# 2_MCU.net
KiCad netlist of a schematic drawn in Altium Designer
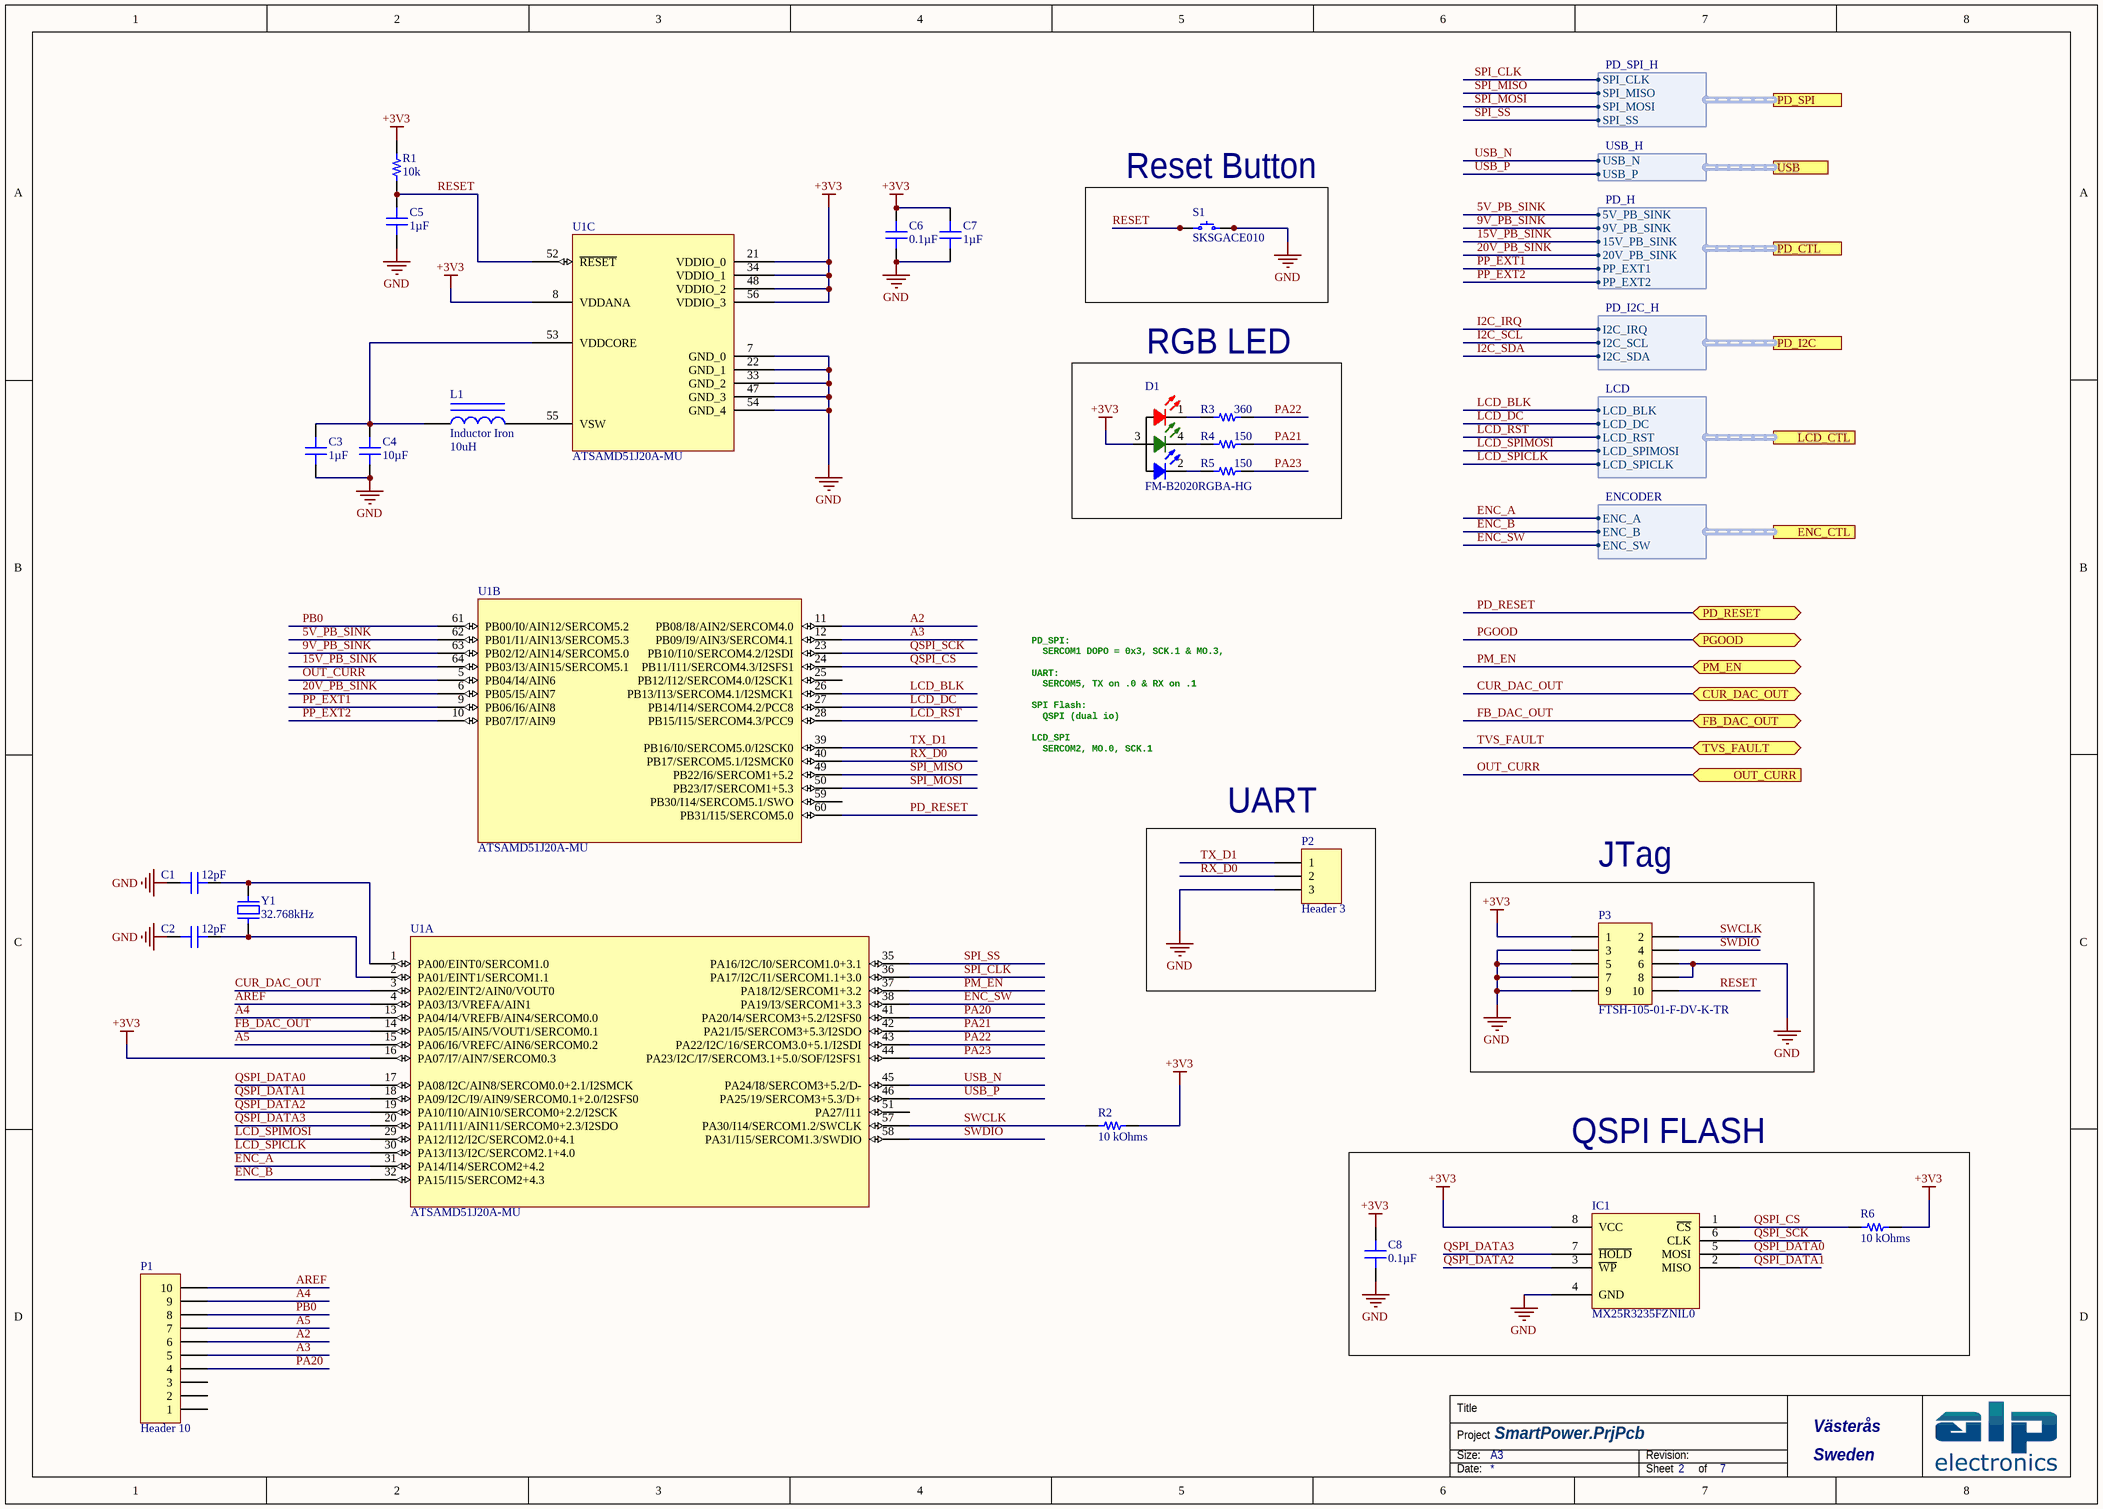
[diagram p0: [2] MCU.SchDoc]

(export (version "E")
  (design (tool "Eeschema 10.0.6"))
  (components
    (comp (ref "C1")
      (value "12pF")
      (footprint "CAP 0603_1608")
      (description "CAP CER 12PF 100V NP0 0603")
      (fields (field (name "PART NUMBER") "06031A120JAT4A") (field (name "MANUFACTURER") "AVX Corporation"))
      (libsource (lib "Celestial Altium Library - altium_library") (part "Capacitor"))
    )
    (comp (ref "C2")
      (value "12pF")
      (footprint "CAP 0603_1608")
      (description "CAP CER 12PF 100V NP0 0603")
      (fields (field (name "PART NUMBER") "06031A120JAT4A") (field (name "MANUFACTURER") "AVX Corporation"))
      (libsource (lib "Celestial Altium Library - altium_library") (part "Capacitor"))
    )
    (comp (ref "C3")
      (value "1µF")
      (footprint "CAP 0603_1608")
      (description "CAP CER 1UF 50V X7R 0603")
      (fields (field (name "PART NUMBER") "06035C105KAT2A") (field (name "MANUFACTURER") "AVX Corporation"))
      (libsource (lib "Celestial Altium Library - altium_library") (part "Capacitor"))
    )
    (comp (ref "C4")
      (value "10µF")
      (footprint "CAP 0603_1608")
      (description "CAP CER 10UF 10V X5R 0603")
      (fields (field (name "PART NUMBER") "0603ZD106MAT2A") (field (name "MANUFACTURER") "AVX Corporation"))
      (libsource (lib "Celestial Altium Library - altium_library") (part "Capacitor"))
    )
    (comp (ref "C5")
      (value "1µF")
      (footprint "CAP 0603_1608")
      (description "CAP CER 1UF 50V X7R 0603")
      (fields (field (name "PART NUMBER") "06035C105KAT2A") (field (name "MANUFACTURER") "AVX Corporation"))
      (libsource (lib "Celestial Altium Library - altium_library") (part "Capacitor"))
    )
    (comp (ref "C6")
      (value "0.1µF")
      (footprint "CAP 0603_1608")
      (description "CAP CER 0.1UF 50V X7R 0603")
      (fields (field (name "PART NUMBER") "0603BB104K500NGT") (field (name "MANUFACTURER") "Knowles Novacap"))
      (libsource (lib "Celestial Altium Library - altium_library") (part "Capacitor"))
    )
    (comp (ref "C7")
      (value "1µF")
      (footprint "CAP 0603_1608")
      (description "CAP CER 1UF 16V X7R 0603")
      (fields (field (name "PART NUMBER") "0603BB105K160YT") (field (name "MANUFACTURER") "Knowles Novacap"))
      (libsource (lib "Celestial Altium Library - altium_library") (part "Capacitor"))
    )
    (comp (ref "C8")
      (value "0.1µF")
      (footprint "CAP 0603_1608")
      (description "CAP CER 0.1UF 50V X7R 0603")
      (fields (field (name "PART NUMBER") "0603BB104K500NGT") (field (name "MANUFACTURER") "Knowles Novacap"))
      (libsource (lib "Celestial Altium Library - altium_library") (part "Capacitor"))
    )
    (comp (ref "D1")
      (value "FM-B2020RGBA-HG")
      (footprint "FM-B2020RGBA-HG")
      (description "RGB 615~630nmRed,515~535nmGreen,465~480nmBlue 2020")
      (fields (field (name "MANUFACTURER") "Foshan NationStar Optoelectronics"))
      (libsource (lib "Celestial Library Database") (part "RGB LED 4PIN"))
    )
    (comp (ref "IC1")
      (value "MX25R3235FZNIL0")
      (footprint "SPANSION WSON-8 6x5MM")
      (description "IC FLASH MEM 16MB SPI CMOS 8WSON")
      (fields (field (name "PART NUMBER") "S25FL116K0XNFI011") (field (name "MANUFACTURER") "Spansion"))
      (libsource (lib "Celestial Library Database") (part "SPANSION FLASH SPI 8PIN"))
    )
    (comp (ref "L1")
      (value "Inductor Iron")
      (footprint "Component 3D Footprint:IND_Würth_74404020100")
      (description "Magnetic-Core Inductor")
      (fields (field (name "ALTIUM_VALUE") "10uH") (field (name "PUBLISHER") "Altium Limited"))
      (libsource (lib "Miscellaneous Devices") (part "Inductor Iron"))
    )
    (comp (ref "P1")
      (value "Header 10")
      (footprint "HDR1X10")
      (description "Header, 10-Pin")
      (fields (field (name "PUBLISHER") "Altium Limited"))
      (libsource (lib "Miscellaneous Connectors") (part "Header 10"))
    )
    (comp (ref "P2")
      (value "Header 3")
      (footprint "HDR1X3")
      (description "Header, 3-Pin")
      (fields (field (name "PUBLISHER") "Altium Limited"))
      (libsource (lib "Miscellaneous Connectors") (part "Header 3"))
    )
    (comp (ref "P3")
      (value "FTSH-105-01-F-DV-K-TR")
      (footprint "3D FootPrint_Backup:FTSH-105-01-F-DV-K-TR")
      (description "Header, 5-Pin, Dual row")
      (fields (field (name "PUBLISHER") "Altium Limited"))
      (libsource (lib "Miscellaneous Connectors") (part "Header 5X2"))
    )
    (comp (ref "R1")
      (value "10k")
      (footprint "RES 0603/1608")
      (description "RES SMD 10K OHM 5% 1/10W 0603")
      (fields
        (field (name "PART NUMBER") "ERJ-3GEYJ103V")
        (field (name "MANUFACTURER") "Panasonic Electronic Components")
      )
      (libsource (lib "Celestial Library Database") (part "Resistor"))
    )
    (comp (ref "R2")
      (value "10 kOhms")
      (footprint "RES 0603_1608")
      (description "RES SMD 10K OHM 5% 1/10W 0603")
      (fields (field (name "PART NUMBER") "CRCW060310K0JNEA") (field (name "MANUFACTURER") "Vishay Dale"))
      (libsource (lib "Celestial Altium Library - altium_library") (part "Resistor"))
    )
    (comp (ref "R3")
      (value "360")
      (footprint "RES 0603/1608")
      (description "RES SMD 360 OHM 5% 1/10W 0603")
      (fields
        (field (name "PART NUMBER") "ERJ-3GEYJ361V")
        (field (name "MANUFACTURER") "Panasonic Electronic Components")
      )
      (libsource (lib "Celestial Library Database") (part "Resistor"))
    )
    (comp (ref "R4")
      (value "150")
      (footprint "RES 0603/1608")
      (description "RES SMD 150 OHM 5% 1/10W 0603")
      (fields
        (field (name "PART NUMBER") "ERJ-3GEYJ151V")
        (field (name "MANUFACTURER") "Panasonic Electronic Components")
      )
      (libsource (lib "Celestial Library Database") (part "Resistor"))
    )
    (comp (ref "R5")
      (value "150")
      (footprint "RES 0603/1608")
      (description "RES SMD 150 OHM 5% 1/10W 0603")
      (fields
        (field (name "PART NUMBER") "ERJ-3GEYJ151V")
        (field (name "MANUFACTURER") "Panasonic Electronic Components")
      )
      (libsource (lib "Celestial Library Database") (part "Resistor"))
    )
    (comp (ref "R6")
      (value "10 kOhms")
      (footprint "RES 0603_1608")
      (description "RES SMD 10K OHM 5% 1/10W 0603")
      (fields (field (name "PART NUMBER") "CRCW060310K0JNEA") (field (name "MANUFACTURER") "Vishay Dale"))
      (libsource (lib "Celestial Altium Library - altium_library") (part "Resistor"))
    )
    (comp (ref "S1")
      (value "SKSGACE010")
      (footprint "SKSGACE010")
      (description "SWITCH TACTILE SPST-NO 0.05A 16V")
      (fields (field (name "MANUFACTURER") "ALPS"))
      (libsource (lib "Celestial Library Database") (part "SPST-NO 4 PIN"))
    )
    (comp (ref "U1")
      (value "ATSAMD51J20A-MU")
      (footprint "SI LABS QFN-64_S")
      (description "IC MCU 32BIT 1MB FLASH 64VQFN")
      (fields (field (name "MANUFACTURER") "Microchip Technology"))
      (libsource (lib "Celestial Library Database") (part "MicroChip SAM D5x VQFN64"))
    )
    (comp (ref "Y1")
      (value "32.768kHz")
      (footprint "ABRACON ABS07")
      (description "CRYSTAL 32.7680KHZ 12.5PF SMD")
      (fields (field (name "PART NUMBER") "ABS07-32.768KHZ-T") (field (name "MANUFACTURER") "Abracon LLC"))
      (libsource (lib "Celestial Library Database") (part "Abracon Crystal ABS07"))
    )
  )
  (nets
    (net (code "7") (name "+3V3") (class "Default")
      (node (ref "C6") (pin "1") (pinfunction "1_1") (pintype "passive"))
      (node (ref "C7") (pin "2") (pinfunction "2_2") (pintype "passive"))
      (node (ref "C8") (pin "1") (pinfunction "1_1") (pintype "passive"))
      (node (ref "D1") (pin "3") (pinfunction "3_3") (pintype "passive"))
      (node (ref "IC1") (pin "8") (pinfunction "VCC_8") (pintype "passive"))
      (node (ref "P3") (pin "1") (pinfunction "1_1") (pintype "passive"))
      (node (ref "R1") (pin "2") (pinfunction "2_2") (pintype "passive"))
      (node (ref "R2") (pin "2") (pinfunction "2_2") (pintype "passive"))
      (node (ref "R6") (pin "2") (pinfunction "2_2") (pintype "passive"))
      (node (ref "U1") (pin "16") (pinfunction "PA07/I7/AIN7/SERCOM0.3_16") (pintype "bidirectional"))
      (node (ref "U1") (pin "21") (pinfunction "VDDIO_0_21") (pintype "power_in"))
      (node (ref "U1") (pin "34") (pinfunction "VDDIO_1_34") (pintype "power_in"))
      (node (ref "U1") (pin "48") (pinfunction "VDDIO_2_48") (pintype "power_in"))
      (node (ref "U1") (pin "56") (pinfunction "VDDIO_3_56") (pintype "power_in"))
      (node (ref "U1") (pin "8") (pinfunction "VDDANA_8") (pintype "power_in"))
    )
    (net (code "8") (name "/5V_PB_SINK") (class "Default")
      (node (ref "U1") (pin "62") (pinfunction "PB01/I1/AIN13/SERCOM5.3_62") (pintype "bidirectional"))
    )
    (net (code "9") (name "/9V_PB_SINK") (class "Default")
      (node (ref "U1") (pin "63") (pinfunction "PB02/I2/AIN14/SERCOM5.0_63") (pintype "bidirectional"))
    )
    (net (code "10") (name "/15V_PB_SINK") (class "Default")
      (node (ref "U1") (pin "64") (pinfunction "PB03/I3/AIN15/SERCOM5.1_64") (pintype "bidirectional"))
    )
    (net (code "11") (name "/20V_PB_SINK") (class "Default")
      (node (ref "U1") (pin "6") (pinfunction "PB05/I5/AIN7_6") (pintype "bidirectional"))
    )
    (net (code "12") (name "/A2") (class "Default")
      (node (ref "P1") (pin "6") (pinfunction "6_6") (pintype "passive"))
      (node (ref "U1") (pin "11") (pinfunction "PB08/I8/AIN2/SERCOM4.0_11") (pintype "bidirectional"))
    )
    (net (code "13") (name "/A3") (class "Default")
      (node (ref "P1") (pin "5") (pinfunction "5_5") (pintype "passive"))
      (node (ref "U1") (pin "12") (pinfunction "PB09/I9/AIN3/SERCOM4.1_12") (pintype "bidirectional"))
    )
    (net (code "14") (name "/A4") (class "Default")
      (node (ref "P1") (pin "9") (pinfunction "9_9") (pintype "passive"))
      (node (ref "U1") (pin "13") (pinfunction "PA04/I4/VREFB/AIN4/SERCOM0.0_13") (pintype "bidirectional"))
    )
    (net (code "15") (name "/A5") (class "Default")
      (node (ref "P1") (pin "7") (pinfunction "7_7") (pintype "passive"))
      (node (ref "U1") (pin "15") (pinfunction "PA06/I6/VREFC/AIN6/SERCOM0.2_15") (pintype "bidirectional"))
    )
    (net (code "16") (name "/AREF") (class "Default")
      (node (ref "P1") (pin "10") (pinfunction "10_10") (pintype "passive"))
      (node (ref "U1") (pin "4") (pinfunction "PA03/I3/VREFA/AIN1_4") (pintype "bidirectional"))
    )
    (net (code "17") (name "/CUR_DAC_OUT") (class "Default")
      (node (ref "U1") (pin "3") (pinfunction "PA02/EINT2/AIN0/VOUT0_3") (pintype "bidirectional"))
    )
    (net (code "18") (name "/ENC_A") (class "Default")
      (node (ref "U1") (pin "31") (pinfunction "PA14/I14/SERCOM2+4.2_31") (pintype "bidirectional"))
    )
    (net (code "19") (name "/ENC_B") (class "Default")
      (node (ref "U1") (pin "32") (pinfunction "PA15/I15/SERCOM2+4.3_32") (pintype "bidirectional"))
    )
    (net (code "20") (name "/ENC_SW") (class "Default")
      (node (ref "U1") (pin "38") (pinfunction "PA19/I3/SERCOM1+3.3_38") (pintype "bidirectional"))
    )
    (net (code "21") (name "/FB_DAC_OUT") (class "Default")
      (node (ref "U1") (pin "14") (pinfunction "PA05/I5/AIN5/VOUT1/SERCOM0.1_14") (pintype "bidirectional"))
    )
    (net (code "25") (name "/LCD_BLK") (class "Default")
      (node (ref "U1") (pin "26") (pinfunction "PB13/I13/SERCOM4.1/I2SMCK1_26") (pintype "bidirectional"))
    )
    (net (code "26") (name "/LCD_DC") (class "Default")
      (node (ref "U1") (pin "27") (pinfunction "PB14/I14/SERCOM4.2/PCC8_27") (pintype "bidirectional"))
    )
    (net (code "27") (name "/LCD_RST") (class "Default")
      (node (ref "U1") (pin "28") (pinfunction "PB15/I15/SERCOM4.3/PCC9_28") (pintype "bidirectional"))
    )
    (net (code "28") (name "/LCD_SPICLK") (class "Default")
      (node (ref "U1") (pin "30") (pinfunction "PA13/I13/I2C/SERCOM2.1+4.0_30") (pintype "bidirectional"))
    )
    (net (code "29") (name "/LCD_SPIMOSI") (class "Default")
      (node (ref "U1") (pin "29") (pinfunction "PA12/I12/I2C/SERCOM2.0+4.1_29") (pintype "bidirectional"))
    )
    (net (code "30") (name "/OUT_CURR") (class "Default")
      (node (ref "U1") (pin "5") (pinfunction "PB04/I4/AIN6_5") (pintype "bidirectional"))
    )
    (net (code "31") (name "/PA20") (class "Default")
      (node (ref "P1") (pin "4") (pinfunction "4_4") (pintype "passive"))
      (node (ref "U1") (pin "41") (pinfunction "PA20/I4/SERCOM3+5.2/I2SFS0_41") (pintype "bidirectional"))
    )
    (net (code "32") (name "/PA21") (class "Default")
      (node (ref "R4") (pin "2") (pinfunction "2_2") (pintype "passive"))
      (node (ref "U1") (pin "42") (pinfunction "PA21/I5/SERCOM3+5.3/I2SDO_42") (pintype "bidirectional"))
    )
    (net (code "33") (name "/PA22") (class "Default")
      (node (ref "R3") (pin "2") (pinfunction "2_2") (pintype "passive"))
      (node (ref "U1") (pin "43") (pinfunction "PA22/I2C/16/SERCOM3.0+5.1/I2SDI_43") (pintype "bidirectional"))
    )
    (net (code "34") (name "/PA23") (class "Default")
      (node (ref "R5") (pin "2") (pinfunction "2_2") (pintype "passive"))
      (node (ref "U1") (pin "44") (pinfunction "PA23/I2C/I7/SERCOM3.1+5.0/SOF/I2SFS1_44") (pintype "bidirectional"))
    )
    (net (code "35") (name "/PB0") (class "Default")
      (node (ref "P1") (pin "8") (pinfunction "8_8") (pintype "passive"))
      (node (ref "U1") (pin "61") (pinfunction "PB00/I0/AIN12/SERCOM5.2_61") (pintype "bidirectional"))
    )
    (net (code "36") (name "/PD_RESET") (class "Default")
      (node (ref "U1") (pin "60") (pinfunction "PB31/I15/SERCOM5.0_60") (pintype "bidirectional"))
    )
    (net (code "38") (name "/PM_EN") (class "Default")
      (node (ref "U1") (pin "37") (pinfunction "PA18/I2/SERCOM1+3.2_37") (pintype "bidirectional"))
    )
    (net (code "39") (name "/PP_EXT1") (class "Default")
      (node (ref "U1") (pin "9") (pinfunction "PB06/I6/AIN8_9") (pintype "bidirectional"))
    )
    (net (code "40") (name "/PP_EXT2") (class "Default")
      (node (ref "U1") (pin "10") (pinfunction "PB07/I7/AIN9_10") (pintype "bidirectional"))
    )
    (net (code "41") (name "/QSPI_CS") (class "Default")
      (node (ref "IC1") (pin "1") (pinfunction "~{CS}_1") (pintype "passive"))
      (node (ref "R6") (pin "1") (pinfunction "1_1") (pintype "passive"))
      (node (ref "U1") (pin "24") (pinfunction "PB11/I11/SERCOM4.3/I2SFS1_24") (pintype "bidirectional"))
    )
    (net (code "42") (name "/QSPI_DATA0") (class "Default")
      (node (ref "IC1") (pin "5") (pinfunction "MOSI_5") (pintype "passive"))
      (node (ref "U1") (pin "17") (pinfunction "PA08/I2C/AIN8/SERCOM0.0+2.1/I2SMCK_17") (pintype "bidirectional"))
    )
    (net (code "43") (name "/QSPI_DATA1") (class "Default")
      (node (ref "IC1") (pin "2") (pinfunction "MISO_2") (pintype "passive"))
      (node (ref "U1") (pin "18") (pinfunction "PA09/I2C/I9/AIN9/SERCOM0.1+2.0/I2SFS0_18") (pintype "bidirectional"))
    )
    (net (code "44") (name "/QSPI_DATA2") (class "Default")
      (node (ref "IC1") (pin "3") (pinfunction "~{WP}_3") (pintype "passive"))
      (node (ref "U1") (pin "19") (pinfunction "PA10/I10/AIN10/SERCOM0+2.2/I2SCK_19") (pintype "bidirectional"))
    )
    (net (code "45") (name "/QSPI_DATA3") (class "Default")
      (node (ref "IC1") (pin "7") (pinfunction "~{HOLD}_7") (pintype "passive"))
      (node (ref "U1") (pin "20") (pinfunction "PA11/I11/AIN11/SERCOM0+2.3/I2SDO_20") (pintype "bidirectional"))
    )
    (net (code "46") (name "/QSPI_SCK") (class "Default")
      (node (ref "IC1") (pin "6") (pinfunction "CLK_6") (pintype "passive"))
      (node (ref "U1") (pin "23") (pinfunction "PB10/I10/SERCOM4.2/I2SDI_23") (pintype "bidirectional"))
    )
    (net (code "47") (name "/RESET") (class "Default")
      (node (ref "C5") (pin "2") (pinfunction "2_2") (pintype "passive"))
      (node (ref "P3") (pin "10") (pinfunction "10_10") (pintype "passive"))
      (node (ref "R1") (pin "1") (pinfunction "1_1") (pintype "passive"))
      (node (ref "S1") (pin "1") (pinfunction "1_1") (pintype "passive"))
      (node (ref "S1") (pin "2") (pinfunction "2_2") (pintype "passive"))
      (node (ref "U1") (pin "52") (pinfunction "~{RESET}_52") (pintype "bidirectional"))
    )
    (net (code "48") (name "/RX_D0") (class "Default")
      (node (ref "P2") (pin "2") (pinfunction "2_2") (pintype "passive"))
      (node (ref "U1") (pin "40") (pinfunction "PB17/SERCOM5.1/I2SMCK0_40") (pintype "bidirectional"))
    )
    (net (code "49") (name "/SPI_CLK") (class "Default")
      (node (ref "U1") (pin "36") (pinfunction "PA17/I2C/I1/SERCOM1.1+3.0_36") (pintype "bidirectional"))
    )
    (net (code "50") (name "/SPI_MISO") (class "Default")
      (node (ref "U1") (pin "49") (pinfunction "PB22/I6/SERCOM1+5.2_49") (pintype "bidirectional"))
    )
    (net (code "51") (name "/SPI_MOSI") (class "Default")
      (node (ref "U1") (pin "50") (pinfunction "PB23/I7/SERCOM1+5.3_50") (pintype "bidirectional"))
    )
    (net (code "52") (name "/SPI_SS") (class "Default")
      (node (ref "U1") (pin "35") (pinfunction "PA16/I2C/I0/SERCOM1.0+3.1_35") (pintype "bidirectional"))
    )
    (net (code "53") (name "/SWCLK") (class "Default")
      (node (ref "P3") (pin "2") (pinfunction "2_2") (pintype "passive"))
      (node (ref "R2") (pin "1") (pinfunction "1_1") (pintype "passive"))
      (node (ref "U1") (pin "57") (pinfunction "PA30/I14/SERCOM1.2/SWCLK_57") (pintype "bidirectional"))
    )
    (net (code "54") (name "/SWDIO") (class "Default")
      (node (ref "P3") (pin "4") (pinfunction "4_4") (pintype "passive"))
      (node (ref "U1") (pin "58") (pinfunction "PA31/I15/SERCOM1.3/SWDIO_58") (pintype "bidirectional"))
    )
    (net (code "56") (name "/TX_D1") (class "Default")
      (node (ref "P2") (pin "1") (pinfunction "1_1") (pintype "passive"))
      (node (ref "U1") (pin "39") (pinfunction "PB16/I0/SERCOM5.0/I2SCK0_39") (pintype "bidirectional"))
    )
    (net (code "57") (name "/USB_N") (class "Default")
      (node (ref "U1") (pin "45") (pinfunction "PA24/I8/SERCOM3+5.2/D-_45") (pintype "bidirectional"))
    )
    (net (code "58") (name "/USB_P") (class "Default")
      (node (ref "U1") (pin "46") (pinfunction "PA25/19/SERCOM3+5.3/D+_46") (pintype "bidirectional"))
    )
    (net (code "65") (name "GND") (class "Default")
      (node (ref "C1") (pin "1") (pinfunction "1_1") (pintype "passive"))
      (node (ref "C2") (pin "1") (pinfunction "1_1") (pintype "passive"))
      (node (ref "C3") (pin "1") (pinfunction "1_1") (pintype "passive"))
      (node (ref "C4") (pin "1") (pinfunction "1_1") (pintype "passive"))
      (node (ref "C5") (pin "1") (pinfunction "1_1") (pintype "passive"))
      (node (ref "C6") (pin "2") (pinfunction "2_2") (pintype "passive"))
      (node (ref "C7") (pin "1") (pinfunction "1_1") (pintype "passive"))
      (node (ref "C8") (pin "2") (pinfunction "2_2") (pintype "passive"))
      (node (ref "IC1") (pin "4") (pinfunction "GND_4") (pintype "passive"))
      (node (ref "P2") (pin "3") (pinfunction "3_3") (pintype "passive"))
      (node (ref "P3") (pin "3") (pinfunction "3_3") (pintype "passive"))
      (node (ref "P3") (pin "5") (pinfunction "5_5") (pintype "passive"))
      (node (ref "P3") (pin "6") (pinfunction "6_6") (pintype "passive"))
      (node (ref "P3") (pin "7") (pinfunction "7_7") (pintype "passive"))
      (node (ref "P3") (pin "8") (pinfunction "8_8") (pintype "passive"))
      (node (ref "P3") (pin "9") (pinfunction "9_9") (pintype "passive"))
      (node (ref "S1") (pin "3") (pinfunction "3_3") (pintype "passive"))
      (node (ref "S1") (pin "4") (pinfunction "4_4") (pintype "passive"))
      (node (ref "U1") (pin "22") (pinfunction "GND_1_22") (pintype "power_in"))
      (node (ref "U1") (pin "33") (pinfunction "GND_2_33") (pintype "power_in"))
      (node (ref "U1") (pin "47") (pinfunction "GND_3_47") (pintype "power_in"))
      (node (ref "U1") (pin "54") (pinfunction "GND_4_54") (pintype "power_in"))
      (node (ref "U1") (pin "7") (pinfunction "GND_0_7") (pintype "power_in"))
    )
    (net (code "66") (name "Net-(D1-Pad1)") (class "Default")
      (node (ref "D1") (pin "1") (pinfunction "1_1") (pintype "passive"))
      (node (ref "R3") (pin "1") (pinfunction "1_1") (pintype "passive"))
    )
    (net (code "67") (name "Net-(D1-Pad2)") (class "Default")
      (node (ref "D1") (pin "2") (pinfunction "2_2") (pintype "passive"))
      (node (ref "R5") (pin "1") (pinfunction "1_1") (pintype "passive"))
    )
    (net (code "68") (name "Net-(D1-Pad4)") (class "Default")
      (node (ref "D1") (pin "4") (pinfunction "4_4") (pintype "passive"))
      (node (ref "R4") (pin "1") (pinfunction "1_1") (pintype "passive"))
    )
    (net (code "69") (name "Net-(U1A-PA00{slash}EINT0{slash}SERCOM1.0)") (class "Default")
      (node (ref "C1") (pin "2") (pinfunction "2_2") (pintype "passive"))
      (node (ref "U1") (pin "1") (pinfunction "PA00/EINT0/SERCOM1.0_1") (pintype "bidirectional"))
      (node (ref "Y1") (pin "2") (pinfunction "2_2") (pintype "passive"))
    )
    (net (code "70") (name "Net-(U1A-PA01{slash}EINT1{slash}SERCOM1.1)") (class "Default")
      (node (ref "C2") (pin "2") (pinfunction "2_2") (pintype "passive"))
      (node (ref "U1") (pin "2") (pinfunction "PA01/EINT1/SERCOM1.1_2") (pintype "bidirectional"))
      (node (ref "Y1") (pin "1") (pinfunction "1_1") (pintype "passive"))
    )
    (net (code "71") (name "Net-(U1C-VDDCORE)") (class "Default")
      (node (ref "C3") (pin "2") (pinfunction "2_2") (pintype "passive"))
      (node (ref "C4") (pin "2") (pinfunction "2_2") (pintype "passive"))
      (node (ref "L1") (pin "1") (pinfunction "1_1") (pintype "passive"))
      (node (ref "U1") (pin "53") (pinfunction "VDDCORE_53") (pintype "power_in"))
    )
    (net (code "72") (name "Net-(U1C-VSW)") (class "Default")
      (node (ref "L1") (pin "2") (pinfunction "2_2") (pintype "passive"))
      (node (ref "U1") (pin "55") (pinfunction "VSW_55") (pintype "power_in"))
    )
    (net (code "73") (name "unconnected-(P1-Pad1)") (class "Default")
      (node (ref "P1") (pin "1") (pinfunction "1_1") (pintype "passive"))
    )
    (net (code "74") (name "unconnected-(P1-Pad2)") (class "Default")
      (node (ref "P1") (pin "2") (pinfunction "2_2") (pintype "passive"))
    )
    (net (code "75") (name "unconnected-(P1-Pad3)") (class "Default")
      (node (ref "P1") (pin "3") (pinfunction "3_3") (pintype "passive"))
    )
    (net (code "76") (name "unconnected-(U1A-PA27{slash}I11-Pad51)") (class "Default")
      (node (ref "U1") (pin "51") (pinfunction "PA27/I11_51") (pintype "bidirectional"))
    )
    (net (code "77") (name "unconnected-(U1B-PB12{slash}I12{slash}SERCOM4.0{slash}I2SCK1-Pad25)") (class "Default")
      (node (ref "U1") (pin "25") (pinfunction "PB12/I12/SERCOM4.0/I2SCK1_25") (pintype "bidirectional"))
    )
    (net (code "78") (name "unconnected-(U1B-PB30{slash}I14{slash}SERCOM5.1{slash}SWO-Pad59)") (class "Default")
      (node (ref "U1") (pin "59") (pinfunction "PB30/I14/SERCOM5.1/SWO_59") (pintype "bidirectional"))
    )
  )
)
